# PyroelectricSensor.net
KiCad netlist of a schematic drawn in EAGLE
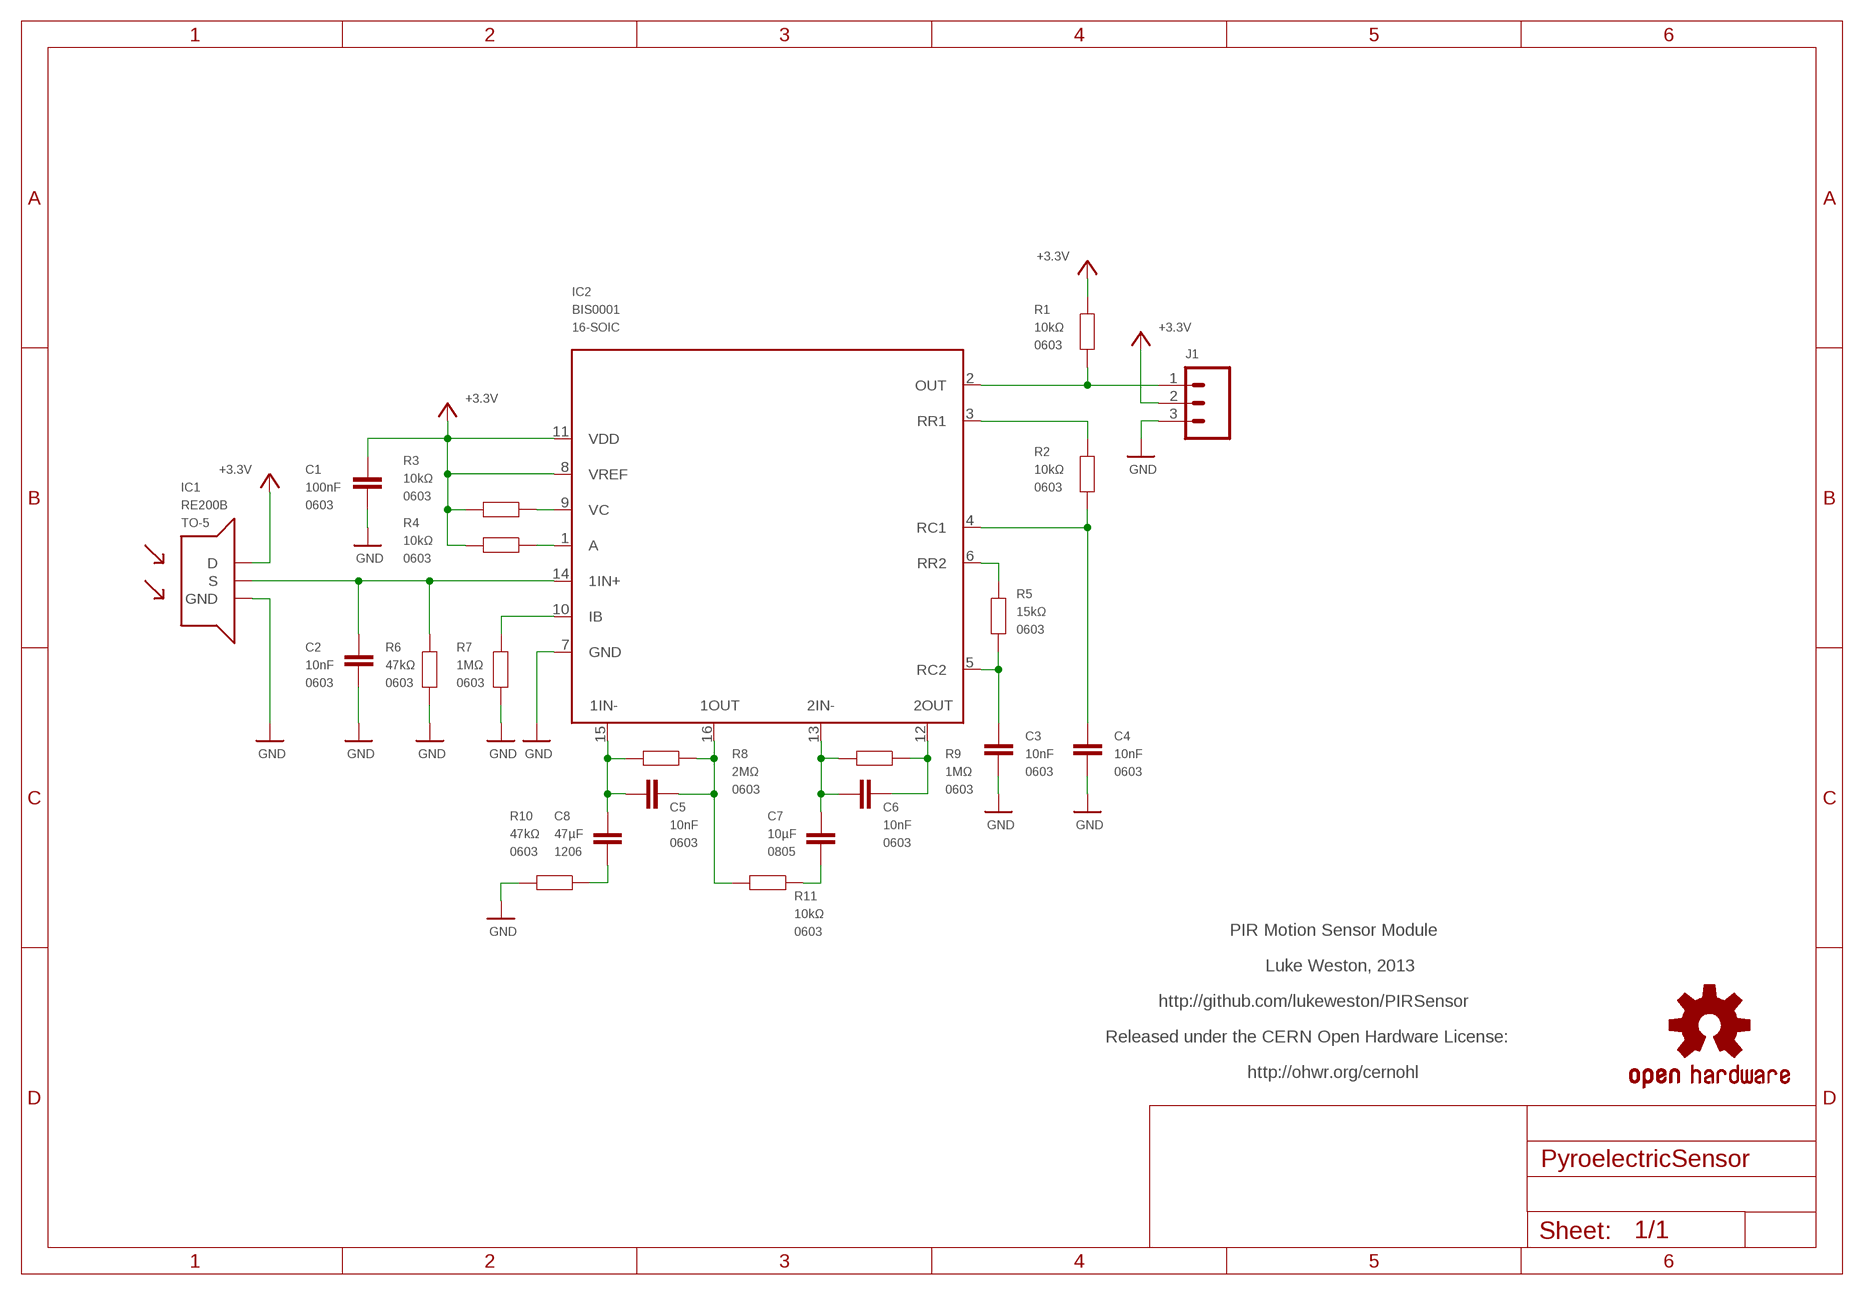
[diagram p0: schematic, sheet 1]

(export (version "E")
  (design (tool "Eeschema 10.0.6"))
  (components
    (comp (ref "C1")
      (value "100nF")
      (footprint "eagle-import:0603")
      (fields (field (name "PACKAGE") "0603"))
      (libsource (lib "eagle-import") (part "CAP0603"))
    )
    (comp (ref "C2")
      (value "10nF")
      (footprint "eagle-import:0603")
      (fields (field (name "PACKAGE") "0603"))
      (libsource (lib "eagle-import") (part "CAP0603"))
    )
    (comp (ref "C3")
      (value "10nF")
      (footprint "eagle-import:0603")
      (fields (field (name "PACKAGE") "0603"))
      (libsource (lib "eagle-import") (part "CAP0603"))
    )
    (comp (ref "C4")
      (value "10nF")
      (footprint "eagle-import:0603")
      (fields (field (name "PACKAGE") "0603"))
      (libsource (lib "eagle-import") (part "CAP0603"))
    )
    (comp (ref "C5")
      (value "10nF")
      (footprint "eagle-import:0603")
      (fields (field (name "PACKAGE") "0603"))
      (libsource (lib "eagle-import") (part "CAP0603"))
    )
    (comp (ref "C6")
      (value "10nF")
      (footprint "eagle-import:0603")
      (fields (field (name "PACKAGE") "0603"))
      (libsource (lib "eagle-import") (part "CAP0603"))
    )
    (comp (ref "C7")
      (value "10µF")
      (footprint "eagle-import:0805")
      (fields (field (name "PACKAGE") "0805"))
      (libsource (lib "eagle-import") (part "CAP0805"))
    )
    (comp (ref "C8")
      (value "47µF")
      (footprint "eagle-import:C1206K")
      (fields (field (name "PACKAGE") "1206"))
      (libsource (lib "eagle-import") (part "C-EUC1206K"))
    )
    (comp (ref "IC1")
      (value "RE200B")
      (footprint "eagle-import:TO5-CAN")
      (fields (field (name "PACKAGE") "TO-5"))
      (libsource (lib "eagle-import") (part "RE200B"))
    )
    (comp (ref "IC2")
      (value "BIS0001")
      (footprint "eagle-import:16-SOIC")
      (fields (field (name "PACKAGE") "16-SOIC"))
      (libsource (lib "eagle-import") (part "BIS0001"))
    )
    (comp (ref "J1")
      (value "M03PTH")
      (footprint "eagle-import:1X03")
      (libsource (lib "eagle-import") (part "M03PTH"))
    )
    (comp (ref "R1")
      (value "10kΩ")
      (footprint "eagle-import:0603")
      (fields (field (name "PACKAGE") "0603"))
      (libsource (lib "eagle-import") (part "RESISTOR0603"))
    )
    (comp (ref "R2")
      (value "10kΩ")
      (footprint "eagle-import:0603")
      (fields (field (name "PACKAGE") "0603"))
      (libsource (lib "eagle-import") (part "RESISTOR0603"))
    )
    (comp (ref "R3")
      (value "10kΩ")
      (footprint "eagle-import:0603")
      (fields (field (name "PACKAGE") "0603"))
      (libsource (lib "eagle-import") (part "RESISTOR0603"))
    )
    (comp (ref "R4")
      (value "10kΩ")
      (footprint "eagle-import:0603")
      (fields (field (name "PACKAGE") "0603"))
      (libsource (lib "eagle-import") (part "RESISTOR0603"))
    )
    (comp (ref "R5")
      (value "15kΩ")
      (footprint "eagle-import:0603")
      (fields (field (name "PACKAGE") "0603"))
      (libsource (lib "eagle-import") (part "RESISTOR0603"))
    )
    (comp (ref "R6")
      (value "47kΩ")
      (footprint "eagle-import:0603")
      (fields (field (name "PACKAGE") "0603"))
      (libsource (lib "eagle-import") (part "RESISTOR0603"))
    )
    (comp (ref "R7")
      (value "1MΩ")
      (footprint "eagle-import:0603")
      (fields (field (name "PACKAGE") "0603"))
      (libsource (lib "eagle-import") (part "RESISTOR0603"))
    )
    (comp (ref "R8")
      (value "2MΩ")
      (footprint "eagle-import:0603")
      (fields (field (name "PACKAGE") "0603"))
      (libsource (lib "eagle-import") (part "RESISTOR0603"))
    )
    (comp (ref "R9")
      (value "1MΩ")
      (footprint "eagle-import:0603")
      (fields (field (name "PACKAGE") "0603"))
      (libsource (lib "eagle-import") (part "RESISTOR0603"))
    )
    (comp (ref "R10")
      (value "47kΩ")
      (footprint "eagle-import:0603")
      (fields (field (name "PACKAGE") "0603"))
      (libsource (lib "eagle-import") (part "RESISTOR0603"))
    )
    (comp (ref "R11")
      (value "10kΩ")
      (footprint "eagle-import:0603")
      (fields (field (name "PACKAGE") "0603"))
      (libsource (lib "eagle-import") (part "RESISTOR0603"))
    )
    (comp (ref "SY")
      (value "OSHW-LOGOS")
      (footprint "eagle-import:OSHW-LOGO-S")
      (libsource (lib "eagle-import") (part "OSHW-LOGOS"))
    )
  )
  (nets
    (net (code "1") (name "+3.3V") (class "Default")
      (node (ref "C1") (pin "1") (pinfunction "1_1") (pintype "passive"))
      (node (ref "IC1") (pin "1") (pinfunction "D_1") (pintype "bidirectional"))
      (node (ref "IC2") (pin "11") (pinfunction "VDD_11") (pintype "bidirectional"))
      (node (ref "IC2") (pin "8") (pinfunction "VREF_8") (pintype "bidirectional"))
      (node (ref "J1") (pin "2") (pinfunction "2_2") (pintype "passive"))
      (node (ref "R1") (pin "2") (pinfunction "2_2") (pintype "passive"))
      (node (ref "R3") (pin "2") (pinfunction "2_2") (pintype "passive"))
      (node (ref "R4") (pin "2") (pinfunction "2_2") (pintype "passive"))
    )
    (net (code "2") (name "GND") (class "Default")
      (node (ref "C1") (pin "2") (pinfunction "2_2") (pintype "passive"))
      (node (ref "C2") (pin "2") (pinfunction "2_2") (pintype "passive"))
      (node (ref "C3") (pin "2") (pinfunction "2_2") (pintype "passive"))
      (node (ref "C4") (pin "2") (pinfunction "2_2") (pintype "passive"))
      (node (ref "IC1") (pin "3") (pinfunction "GND_3") (pintype "bidirectional"))
      (node (ref "IC2") (pin "7") (pinfunction "GND_7") (pintype "bidirectional"))
      (node (ref "J1") (pin "3") (pinfunction "3_3") (pintype "passive"))
      (node (ref "R10") (pin "2") (pinfunction "2_2") (pintype "passive"))
      (node (ref "R6") (pin "1") (pinfunction "1_1") (pintype "passive"))
      (node (ref "R7") (pin "1") (pinfunction "1_1") (pintype "passive"))
    )
    (net (code "3") (name "Net-(C7-Pad1)") (class "Default")
      (node (ref "C7") (pin "1") (pinfunction "1_1") (pintype "passive"))
      (node (ref "R11") (pin "1") (pinfunction "1_1") (pintype "passive"))
    )
    (net (code "4") (name "Net-(C8-Pad1)") (class "Default")
      (node (ref "C8") (pin "1") (pinfunction "1_1") (pintype "passive"))
      (node (ref "R10") (pin "1") (pinfunction "1_1") (pintype "passive"))
    )
    (net (code "5") (name "Net-(IC1-S)") (class "Default")
      (node (ref "C2") (pin "1") (pinfunction "1_1") (pintype "passive"))
      (node (ref "IC1") (pin "2") (pinfunction "S_2") (pintype "bidirectional"))
      (node (ref "IC2") (pin "14") (pinfunction "1IN+_14") (pintype "bidirectional"))
      (node (ref "R6") (pin "2") (pinfunction "2_2") (pintype "passive"))
    )
    (net (code "6") (name "Net-(IC2-1IN-)") (class "Default")
      (node (ref "C5") (pin "1") (pinfunction "1_1") (pintype "passive"))
      (node (ref "C8") (pin "2") (pinfunction "2_2") (pintype "passive"))
      (node (ref "IC2") (pin "15") (pinfunction "1IN-_15") (pintype "bidirectional"))
      (node (ref "R8") (pin "2") (pinfunction "2_2") (pintype "passive"))
    )
    (net (code "7") (name "Net-(IC2-1OUT)") (class "Default")
      (node (ref "C5") (pin "2") (pinfunction "2_2") (pintype "passive"))
      (node (ref "IC2") (pin "16") (pinfunction "1OUT_16") (pintype "bidirectional"))
      (node (ref "R11") (pin "2") (pinfunction "2_2") (pintype "passive"))
      (node (ref "R8") (pin "1") (pinfunction "1_1") (pintype "passive"))
    )
    (net (code "8") (name "Net-(IC2-2IN-)") (class "Default")
      (node (ref "C6") (pin "1") (pinfunction "1_1") (pintype "passive"))
      (node (ref "C7") (pin "2") (pinfunction "2_2") (pintype "passive"))
      (node (ref "IC2") (pin "13") (pinfunction "2IN-_13") (pintype "bidirectional"))
      (node (ref "R9") (pin "2") (pinfunction "2_2") (pintype "passive"))
    )
    (net (code "9") (name "Net-(IC2-2OUT)") (class "Default")
      (node (ref "C6") (pin "2") (pinfunction "2_2") (pintype "passive"))
      (node (ref "IC2") (pin "12") (pinfunction "2OUT_12") (pintype "bidirectional"))
      (node (ref "R9") (pin "1") (pinfunction "1_1") (pintype "passive"))
    )
    (net (code "10") (name "Net-(IC2-A)") (class "Default")
      (node (ref "IC2") (pin "1") (pinfunction "A_1") (pintype "bidirectional"))
      (node (ref "R4") (pin "1") (pinfunction "1_1") (pintype "passive"))
    )
    (net (code "11") (name "Net-(IC2-IB)") (class "Default")
      (node (ref "IC2") (pin "10") (pinfunction "IB_10") (pintype "bidirectional"))
      (node (ref "R7") (pin "2") (pinfunction "2_2") (pintype "passive"))
    )
    (net (code "12") (name "Net-(IC2-OUT)") (class "Default")
      (node (ref "IC2") (pin "2") (pinfunction "OUT_2") (pintype "bidirectional"))
      (node (ref "J1") (pin "1") (pinfunction "1_1") (pintype "passive"))
      (node (ref "R1") (pin "1") (pinfunction "1_1") (pintype "passive"))
    )
    (net (code "13") (name "Net-(IC2-RC1)") (class "Default")
      (node (ref "C4") (pin "1") (pinfunction "1_1") (pintype "passive"))
      (node (ref "IC2") (pin "4") (pinfunction "RC1_4") (pintype "bidirectional"))
      (node (ref "R2") (pin "1") (pinfunction "1_1") (pintype "passive"))
    )
    (net (code "14") (name "Net-(IC2-RC2)") (class "Default")
      (node (ref "C3") (pin "1") (pinfunction "1_1") (pintype "passive"))
      (node (ref "IC2") (pin "5") (pinfunction "RC2_5") (pintype "bidirectional"))
      (node (ref "R5") (pin "1") (pinfunction "1_1") (pintype "passive"))
    )
    (net (code "15") (name "Net-(IC2-RR1)") (class "Default")
      (node (ref "IC2") (pin "3") (pinfunction "RR1_3") (pintype "bidirectional"))
      (node (ref "R2") (pin "2") (pinfunction "2_2") (pintype "passive"))
    )
    (net (code "16") (name "Net-(IC2-RR2)") (class "Default")
      (node (ref "IC2") (pin "6") (pinfunction "RR2_6") (pintype "bidirectional"))
      (node (ref "R5") (pin "2") (pinfunction "2_2") (pintype "passive"))
    )
    (net (code "17") (name "Net-(IC2-VC)") (class "Default")
      (node (ref "IC2") (pin "9") (pinfunction "VC_9") (pintype "bidirectional"))
      (node (ref "R3") (pin "1") (pinfunction "1_1") (pintype "passive"))
    )
  )
)
